# alarm_clock.net
KiCad netlist of a schematic drawn in EAGLE
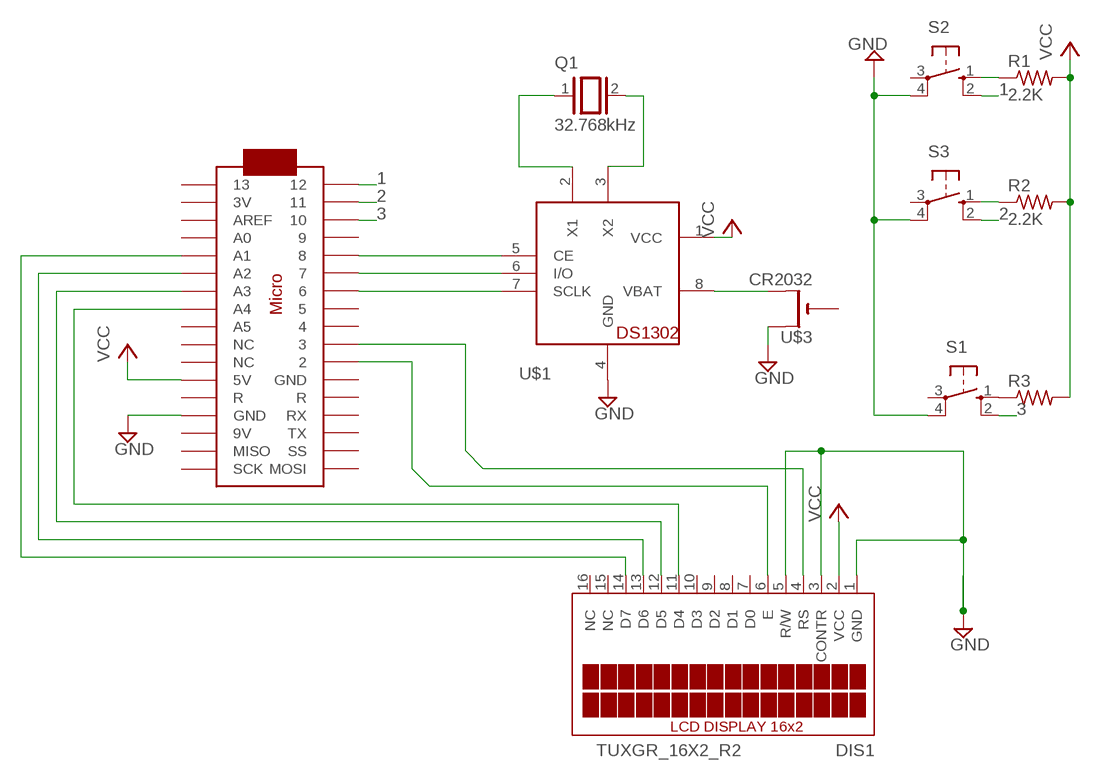
[diagram p0: schematic, sheet 1]

(export (version "E")
  (design (tool "Eeschema 10.0.6"))
  (components
    (comp (ref "DIS1")
      (value "TUXGR_16X2_R2")
      (footprint "eagle-import:TUXGR_16X2_R2")
      (libsource (lib "eagle-import") (part "TUXGR_16X2_R2"))
    )
    (comp (ref "Q1")
      (value "32.768kHz")
      (footprint "eagle-import:Q")
      (libsource (lib "eagle-import") (part "XTAL"))
    )
    (comp (ref "R1")
      (value "2.2K")
      (footprint "eagle-import:0204_7")
      (libsource (lib "eagle-import") (part "R-US_0204/7"))
    )
    (comp (ref "R2")
      (value "2.2K")
      (footprint "eagle-import:0204_7")
      (libsource (lib "eagle-import") (part "R-US_0204/7"))
    )
    (comp (ref "R3")
      (value "R-US_0204/7")
      (footprint "eagle-import:0204_7")
      (libsource (lib "eagle-import") (part "R-US_0204/7"))
    )
    (comp (ref "S1")
      (value "40-XX")
      (footprint "eagle-import:B3F-40XX")
      (fields (field (name "MF") "OMRON COMPONENTS USA") (field (name "MPN") "B3F-4000"))
      (libsource (lib "eagle-import") (part "40-XX"))
    )
    (comp (ref "S2")
      (value "40-XX")
      (footprint "eagle-import:B3F-40XX")
      (fields (field (name "MF") "OMRON COMPONENTS USA") (field (name "MPN") "B3F-4000"))
      (libsource (lib "eagle-import") (part "40-XX"))
    )
    (comp (ref "S3")
      (value "40-XX")
      (footprint "eagle-import:B3F-40XX")
      (fields (field (name "MF") "OMRON COMPONENTS USA") (field (name "MPN") "B3F-4000"))
      (libsource (lib "eagle-import") (part "40-XX"))
    )
    (comp (ref "U$1")
      (value "DS1302")
      (footprint "eagle-import:DIL08-ROUND")
      (libsource (lib "eagle-import") (part "DS1302"))
    )
    (comp (ref "U$2")
      (value "ARDUINOMICRO")
      (footprint "eagle-import:ARDUINOMICRO")
      (libsource (lib "eagle-import") (part "ARDUINOMICRO"))
    )
    (comp (ref "U$3")
      (value "CR2032")
      (footprint "eagle-import:CR2032-SMD")
      (libsource (lib "eagle-import") (part "CR2032SMT"))
    )
  )
  (nets
    (net (code "1") (name "/1") (class "Default")
      (node (ref "S2") (pin "2") (pinfunction "S1_2") (pintype "passive"))
      (node (ref "U$2") (pin "P$1") (pinfunction "12_P$1") (pintype "bidirectional"))
    )
    (net (code "2") (name "/2") (class "Default")
      (node (ref "S3") (pin "2") (pinfunction "S1_2") (pintype "passive"))
      (node (ref "U$2") (pin "P$2") (pinfunction "11_P$2") (pintype "bidirectional"))
    )
    (net (code "3") (name "/3") (class "Default")
      (node (ref "S1") (pin "2") (pinfunction "S1_2") (pintype "passive"))
      (node (ref "U$2") (pin "P$3") (pinfunction "10_P$3") (pintype "bidirectional"))
    )
    (net (code "4") (name "GND") (class "Default")
      (node (ref "DIS1") (pin "1") (pinfunction "GND_1") (pintype "power_in"))
      (node (ref "DIS1") (pin "3") (pinfunction "CONTR_3") (pintype "input"))
      (node (ref "DIS1") (pin "5") (pinfunction "R/W_5") (pintype "input"))
      (node (ref "S1") (pin "4") (pinfunction "P1_4") (pintype "passive"))
      (node (ref "S2") (pin "4") (pinfunction "P1_4") (pintype "passive"))
      (node (ref "S3") (pin "4") (pinfunction "P1_4") (pintype "passive"))
      (node (ref "U$1") (pin "4") (pinfunction "GND_4") (pintype "power_in"))
      (node (ref "U$2") (pin "P$12") (pinfunction "GND_P$12") (pintype "bidirectional"))
      (node (ref "U$3") (pin "+$1") (pinfunction "+_+$1") (pintype "passive"))
    )
    (net (code "5") (name "Net-(DIS1-D4)") (class "Default")
      (node (ref "DIS1") (pin "11") (pinfunction "D4_11") (pintype "input"))
      (node (ref "U$2") (pin "P$27") (pinfunction "A4_P$27") (pintype "bidirectional"))
    )
    (net (code "6") (name "Net-(DIS1-D5)") (class "Default")
      (node (ref "DIS1") (pin "12") (pinfunction "D5_12") (pintype "input"))
      (node (ref "U$2") (pin "P$28") (pinfunction "A3_P$28") (pintype "bidirectional"))
    )
    (net (code "7") (name "Net-(DIS1-D6)") (class "Default")
      (node (ref "DIS1") (pin "13") (pinfunction "D6_13") (pintype "input"))
      (node (ref "U$2") (pin "P$29") (pinfunction "A2_P$29") (pintype "bidirectional"))
    )
    (net (code "8") (name "Net-(DIS1-D7)") (class "Default")
      (node (ref "DIS1") (pin "14") (pinfunction "D7_14") (pintype "input"))
      (node (ref "U$2") (pin "P$30") (pinfunction "A1_P$30") (pintype "bidirectional"))
    )
    (net (code "9") (name "Net-(DIS1-E)") (class "Default")
      (node (ref "DIS1") (pin "6") (pinfunction "E_6") (pintype "input"))
      (node (ref "U$2") (pin "P$11") (pinfunction "2_P$11") (pintype "bidirectional"))
    )
    (net (code "10") (name "Net-(DIS1-RS)") (class "Default")
      (node (ref "DIS1") (pin "4") (pinfunction "RS_4") (pintype "input"))
      (node (ref "U$2") (pin "P$10") (pinfunction "3_P$10") (pintype "bidirectional"))
    )
    (net (code "11") (name "Net-(S1-S)") (class "Default")
      (node (ref "R3") (pin "1") (pinfunction "1_1") (pintype "passive"))
      (node (ref "S1") (pin "1") (pinfunction "S_1") (pintype "passive"))
    )
    (net (code "12") (name "Net-(S2-S)") (class "Default")
      (node (ref "R1") (pin "1") (pinfunction "1_1") (pintype "passive"))
      (node (ref "S2") (pin "1") (pinfunction "S_1") (pintype "passive"))
    )
    (net (code "13") (name "Net-(S3-S)") (class "Default")
      (node (ref "R2") (pin "1") (pinfunction "1_1") (pintype "passive"))
      (node (ref "S3") (pin "1") (pinfunction "S_1") (pintype "passive"))
    )
    (net (code "14") (name "Net-(U$1-CE)") (class "Default")
      (node (ref "U$1") (pin "5") (pinfunction "CE_5") (pintype "input"))
      (node (ref "U$2") (pin "P$5") (pinfunction "8_P$5") (pintype "bidirectional"))
    )
    (net (code "15") (name "Net-(U$1-I{slash}O)") (class "Default")
      (node (ref "U$1") (pin "6") (pinfunction "I/O_6") (pintype "bidirectional"))
      (node (ref "U$2") (pin "P$6") (pinfunction "7_P$6") (pintype "bidirectional"))
    )
    (net (code "16") (name "Net-(U$1-SCLK)") (class "Default")
      (node (ref "U$1") (pin "7") (pinfunction "SCLK_7") (pintype "input"))
      (node (ref "U$2") (pin "P$7") (pinfunction "6_P$7") (pintype "bidirectional"))
    )
    (net (code "17") (name "Net-(U$1-VBAT)") (class "Default")
      (node (ref "U$1") (pin "8") (pinfunction "VBAT_8") (pintype "power_in"))
      (node (ref "U$3") (pin "+$2") (pinfunction "+1_+$2") (pintype "passive"))
    )
    (net (code "18") (name "Net-(U$1-X1)") (class "Default")
      (node (ref "Q1") (pin "1") (pinfunction "1_1") (pintype "passive"))
      (node (ref "U$1") (pin "2") (pinfunction "X1_2") (pintype "passive"))
    )
    (net (code "19") (name "Net-(U$1-X2)") (class "Default")
      (node (ref "Q1") (pin "2") (pinfunction "2_2") (pintype "passive"))
      (node (ref "U$1") (pin "3") (pinfunction "X2_3") (pintype "passive"))
    )
    (net (code "20") (name "VCC") (class "Default")
      (node (ref "DIS1") (pin "2") (pinfunction "VCC_2") (pintype "power_in"))
      (node (ref "R1") (pin "2") (pinfunction "2_2") (pintype "passive"))
      (node (ref "R2") (pin "2") (pinfunction "2_2") (pintype "passive"))
      (node (ref "R3") (pin "2") (pinfunction "2_2") (pintype "passive"))
      (node (ref "U$1") (pin "1") (pinfunction "VCC_1") (pintype "power_in"))
      (node (ref "U$2") (pin "P$23") (pinfunction "5V_P$23") (pintype "bidirectional"))
    )
    (net (code "21") (name "unconnected-(DIS1-D0-Pad7)") (class "Default")
      (node (ref "DIS1") (pin "7") (pinfunction "D0_7") (pintype "input"))
    )
    (net (code "22") (name "unconnected-(DIS1-D1-Pad8)") (class "Default")
      (node (ref "DIS1") (pin "8") (pinfunction "D1_8") (pintype "input"))
    )
    (net (code "23") (name "unconnected-(DIS1-D2-Pad9)") (class "Default")
      (node (ref "DIS1") (pin "9") (pinfunction "D2_9") (pintype "input"))
    )
    (net (code "24") (name "unconnected-(DIS1-D3-Pad10)") (class "Default")
      (node (ref "DIS1") (pin "10") (pinfunction "D3_10") (pintype "input"))
    )
    (net (code "25") (name "unconnected-(DIS1-NC-Pad15)") (class "Default")
      (node (ref "DIS1") (pin "15") (pinfunction "NC_15") (pintype "no_connect"))
    )
    (net (code "26") (name "unconnected-(DIS1-NC-Pad16)") (class "Default")
      (node (ref "DIS1") (pin "16") (pinfunction "NC_16") (pintype "no_connect"))
    )
    (net (code "27") (name "unconnected-(S1-P-Pad3)") (class "Default")
      (node (ref "S1") (pin "3") (pinfunction "P_3") (pintype "passive"))
    )
    (net (code "28") (name "unconnected-(S2-P-Pad3)") (class "Default")
      (node (ref "S2") (pin "3") (pinfunction "P_3") (pintype "passive"))
    )
    (net (code "29") (name "unconnected-(S3-P-Pad3)") (class "Default")
      (node (ref "S3") (pin "3") (pinfunction "P_3") (pintype "passive"))
    )
    (net (code "30") (name "unconnected-(U$2-3V-PadP$33)") (class "Default")
      (node (ref "U$2") (pin "P$33") (pinfunction "3V_P$33") (pintype "bidirectional"))
    )
    (net (code "31") (name "unconnected-(U$2-4-PadP$9)") (class "Default")
      (node (ref "U$2") (pin "P$9") (pinfunction "4_P$9") (pintype "bidirectional"))
    )
    (net (code "32") (name "unconnected-(U$2-5-PadP$8)") (class "Default")
      (node (ref "U$2") (pin "P$8") (pinfunction "5_P$8") (pintype "bidirectional"))
    )
    (net (code "33") (name "unconnected-(U$2-9-PadP$4)") (class "Default")
      (node (ref "U$2") (pin "P$4") (pinfunction "9_P$4") (pintype "bidirectional"))
    )
    (net (code "34") (name "unconnected-(U$2-9V-PadP$20)") (class "Default")
      (node (ref "U$2") (pin "P$20") (pinfunction "9V_P$20") (pintype "bidirectional"))
    )
    (net (code "35") (name "unconnected-(U$2-13-PadP$34)") (class "Default")
      (node (ref "U$2") (pin "P$34") (pinfunction "13_P$34") (pintype "bidirectional"))
    )
    (net (code "36") (name "unconnected-(U$2-A0-PadP$31)") (class "Default")
      (node (ref "U$2") (pin "P$31") (pinfunction "A0_P$31") (pintype "bidirectional"))
    )
    (net (code "37") (name "unconnected-(U$2-A5-PadP$26)") (class "Default")
      (node (ref "U$2") (pin "P$26") (pinfunction "A5_P$26") (pintype "bidirectional"))
    )
    (net (code "38") (name "unconnected-(U$2-AREF-PadP$32)") (class "Default")
      (node (ref "U$2") (pin "P$32") (pinfunction "AREF_P$32") (pintype "bidirectional"))
    )
    (net (code "39") (name "unconnected-(U$2-GND-PadP$21)") (class "Default")
      (node (ref "U$2") (pin "P$21") (pinfunction "GND_P$21") (pintype "bidirectional"))
    )
    (net (code "40") (name "unconnected-(U$2-MISO-PadP$19)") (class "Default")
      (node (ref "U$2") (pin "P$19") (pinfunction "MISO_P$19") (pintype "bidirectional"))
    )
    (net (code "41") (name "unconnected-(U$2-MOSI-PadP$17)") (class "Default")
      (node (ref "U$2") (pin "P$17") (pinfunction "MOSI_P$17") (pintype "bidirectional"))
    )
    (net (code "42") (name "unconnected-(U$2-NC-PadP$24)") (class "Default")
      (node (ref "U$2") (pin "P$24") (pinfunction "NC_P$24") (pintype "bidirectional"))
    )
    (net (code "43") (name "unconnected-(U$2-NC-PadP$25)") (class "Default")
      (node (ref "U$2") (pin "P$25") (pinfunction "NC_P$25") (pintype "bidirectional"))
    )
    (net (code "44") (name "unconnected-(U$2-R-PadP$13)") (class "Default")
      (node (ref "U$2") (pin "P$13") (pinfunction "R_P$13") (pintype "bidirectional"))
    )
    (net (code "45") (name "unconnected-(U$2-R-PadP$22)") (class "Default")
      (node (ref "U$2") (pin "P$22") (pinfunction "R_P$22") (pintype "bidirectional"))
    )
    (net (code "46") (name "unconnected-(U$2-RX-PadP$14)") (class "Default")
      (node (ref "U$2") (pin "P$14") (pinfunction "RX_P$14") (pintype "bidirectional"))
    )
    (net (code "47") (name "unconnected-(U$2-SCK-PadP$18)") (class "Default")
      (node (ref "U$2") (pin "P$18") (pinfunction "SCK_P$18") (pintype "bidirectional"))
    )
    (net (code "48") (name "unconnected-(U$2-SS-PadP$16)") (class "Default")
      (node (ref "U$2") (pin "P$16") (pinfunction "SS_P$16") (pintype "bidirectional"))
    )
    (net (code "49") (name "unconnected-(U$2-TX-PadP$15)") (class "Default")
      (node (ref "U$2") (pin "P$15") (pinfunction "TX_P$15") (pintype "bidirectional"))
    )
    (net (code "50") (name "unconnected-(U$3-Pad-)") (class "Default")
      (node (ref "U$3") (pin "-") (pinfunction "-_-") (pintype "passive"))
    )
  )
)
